# Sheet1.net
KiCad netlist of a schematic drawn in Altium Designer
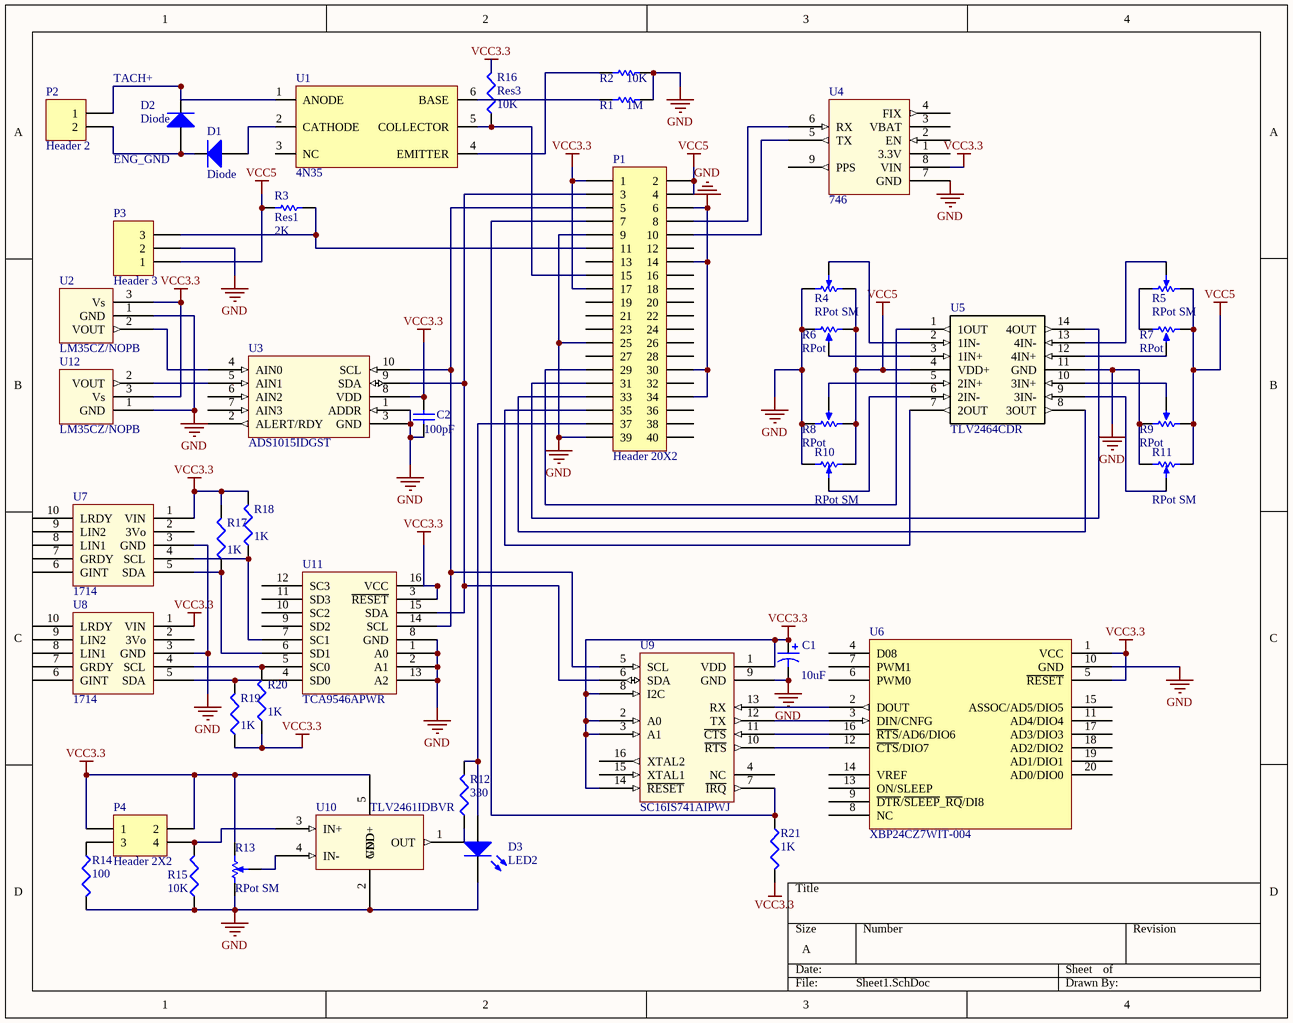
[diagram p0: Sheet1.SchDoc]

(export (version "E")
  (design (tool "Eeschema 10.0.6"))
  (components
    (comp (ref "C1")
      (value "10uF")
      (footprint "C0805")
      (description "Polarized Capacitor (Surface Mount)")
      (fields (field (name "Comment") "Cap Pol3") (field (name "PUBLISHER") "Altium Limited"))
      (libsource (lib "Miscellaneous Devices") (part "Cap Pol3"))
    )
    (comp (ref "C2")
      (value "100pF")
      (footprint "1608[0603]")
      (description "Capacitor (Semiconductor SIM Model)")
      (fields (field (name "Comment") "Cap Semi") (field (name "PUBLISHER") "Altium Limited"))
      (libsource (lib "Miscellaneous Devices") (part "Cap Semi"))
    )
    (comp (ref "D1")
      (value "Diode")
      (footprint "DIODE-0.4")
      (description "Default Diode")
      (fields (field (name "PUBLISHER") "Altium Limited"))
      (libsource (lib "Miscellaneous Devices") (part "Diode"))
    )
    (comp (ref "D2")
      (value "Diode")
      (footprint "DIODE-0.4")
      (description "Default Diode")
      (fields (field (name "PUBLISHER") "Altium Limited"))
      (libsource (lib "Miscellaneous Devices") (part "Diode"))
    )
    (comp (ref "D3")
      (value "LED2")
      (footprint "3.2X1.6X1.1")
      (description "Typical RED, GREEN, YELLOW, AMBER GaAs LED")
      (fields (field (name "PUBLISHER") "Altium Limited"))
      (libsource (lib "Miscellaneous Devices") (part "LED2"))
    )
    (comp (ref "P1")
      (value "Header 20X2")
      (footprint "HDR2X20")
      (description "Header, 20-Pin, Dual row")
      (fields (field (name "PUBLISHER") "Altium Limited"))
      (libsource (lib "Miscellaneous Connectors") (part "Header 20X2"))
    )
    (comp (ref "P2")
      (value "Header 2")
      (footprint "HDR1X2")
      (description "Header, 2-Pin")
      (fields (field (name "PUBLISHER") "Altium Limited"))
      (libsource (lib "Miscellaneous Connectors") (part "Header 2"))
    )
    (comp (ref "P3")
      (value "Header 3")
      (footprint "HDR1X3")
      (description "Header, 3-Pin")
      (fields (field (name "PUBLISHER") "Altium Limited"))
      (libsource (lib "Miscellaneous Connectors") (part "Header 3"))
    )
    (comp (ref "P4")
      (value "Header 2X2")
      (footprint "HDR2X2")
      (description "Header, 2-Pin, Dual row")
      (fields (field (name "PUBLISHER") "Altium Limited"))
      (libsource (lib "Miscellaneous Connectors") (part "Header 2X2"))
    )
    (comp (ref "R1")
      (value "1M")
      (footprint "0402")
      (description "Resistor")
      (fields (field (name "Comment") "Res1") (field (name "PUBLISHER") "Altium Limited"))
      (libsource (lib "Miscellaneous Devices") (part "Res1"))
    )
    (comp (ref "R2")
      (value "10K")
      (footprint "0402")
      (description "Resistor")
      (fields (field (name "Comment") "Res1") (field (name "PUBLISHER") "Altium Limited"))
      (libsource (lib "Miscellaneous Devices") (part "Res1"))
    )
    (comp (ref "R3")
      (value "Res1")
      (footprint "0402")
      (description "Resistor")
      (fields (field (name "ALTIUM_VALUE") "2K") (field (name "PUBLISHER") "Altium Limited"))
      (libsource (lib "Miscellaneous Devices") (part "Res1"))
    )
    (comp (ref "R4")
      (value "RPot SM")
      (footprint "23BR10KLFTR")
      (description "Square Trimming Potentiometer")
      (fields (field (name "PUBLISHER") "Altium Limited"))
      (libsource (lib "Miscellaneous Devices") (part "RPot SM"))
    )
    (comp (ref "R5")
      (value "RPot SM")
      (footprint "23BR10KLFTR")
      (description "Square Trimming Potentiometer")
      (fields (field (name "PUBLISHER") "Altium Limited"))
      (libsource (lib "Miscellaneous Devices") (part "RPot SM"))
    )
    (comp (ref "R6")
      (value "RPot")
      (footprint "VR5")
      (description "Potentiometer")
      (fields (field (name "PUBLISHER") "Altium Limited"))
      (libsource (lib "Miscellaneous Devices") (part "RPot"))
    )
    (comp (ref "R7")
      (value "RPot")
      (footprint "VR5")
      (description "Potentiometer")
      (fields (field (name "PUBLISHER") "Altium Limited"))
      (libsource (lib "Miscellaneous Devices") (part "RPot"))
    )
    (comp (ref "R8")
      (value "RPot")
      (footprint "VR5")
      (description "Potentiometer")
      (fields (field (name "PUBLISHER") "Altium Limited"))
      (libsource (lib "Miscellaneous Devices") (part "RPot"))
    )
    (comp (ref "R9")
      (value "RPot")
      (footprint "VR5")
      (description "Potentiometer")
      (fields (field (name "PUBLISHER") "Altium Limited"))
      (libsource (lib "Miscellaneous Devices") (part "RPot"))
    )
    (comp (ref "R10")
      (value "RPot SM")
      (footprint "23BR10KLFTR")
      (description "Square Trimming Potentiometer")
      (fields (field (name "PUBLISHER") "Altium Limited"))
      (libsource (lib "Miscellaneous Devices") (part "RPot SM"))
    )
    (comp (ref "R11")
      (value "RPot SM")
      (footprint "23BR10KLFTR")
      (description "Square Trimming Potentiometer")
      (fields (field (name "PUBLISHER") "Altium Limited"))
      (libsource (lib "Miscellaneous Devices") (part "RPot SM"))
    )
    (comp (ref "R12")
      (value "330")
      (footprint "0402")
      (description "Resistor")
      (fields (field (name "Comment") "Res3") (field (name "PUBLISHER") "Altium Limited"))
      (libsource (lib "Miscellaneous Devices") (part "Res3"))
    )
    (comp (ref "R13")
      (value "RPot SM")
      (footprint "23BR10KLFTR")
      (description "Square Trimming Potentiometer")
      (fields (field (name "PUBLISHER") "Altium Limited"))
      (libsource (lib "Miscellaneous Devices") (part "RPot SM"))
    )
    (comp (ref "R14")
      (value "100")
      (footprint "0402")
      (description "Resistor")
      (fields (field (name "Comment") "Res3") (field (name "PUBLISHER") "Altium Limited"))
      (libsource (lib "Miscellaneous Devices") (part "Res3"))
    )
    (comp (ref "R15")
      (value "10K")
      (footprint "0402")
      (description "Resistor")
      (fields (field (name "Comment") "Res3") (field (name "PUBLISHER") "Altium Limited"))
      (libsource (lib "Miscellaneous Devices") (part "Res3"))
    )
    (comp (ref "R16")
      (value "Res3")
      (footprint "0402")
      (description "Resistor")
      (fields (field (name "ALTIUM_VALUE") "10K") (field (name "PUBLISHER") "Altium Limited"))
      (libsource (lib "Miscellaneous Devices") (part "Res3"))
    )
    (comp (ref "R17")
      (value "1K")
      (footprint "J1-0603")
      (description "Resistor")
      (fields (field (name "Comment") "Res3") (field (name "PUBLISHER") "Altium Limited"))
      (libsource (lib "Miscellaneous Devices") (part "Res3"))
    )
    (comp (ref "R18")
      (value "1K")
      (footprint "J1-0603")
      (description "Resistor")
      (fields (field (name "Comment") "Res3") (field (name "PUBLISHER") "Altium Limited"))
      (libsource (lib "Miscellaneous Devices") (part "Res3"))
    )
    (comp (ref "R19")
      (value "1K")
      (footprint "J1-0603")
      (description "Resistor")
      (fields (field (name "Comment") "Res3") (field (name "PUBLISHER") "Altium Limited"))
      (libsource (lib "Miscellaneous Devices") (part "Res3"))
    )
    (comp (ref "R20")
      (value "1K")
      (footprint "J1-0603")
      (description "Resistor")
      (fields (field (name "Comment") "Res3") (field (name "PUBLISHER") "Altium Limited"))
      (libsource (lib "Miscellaneous Devices") (part "Res3"))
    )
    (comp (ref "R21")
      (value "1K")
      (footprint "J1-0603")
      (description "Resistor")
      (fields (field (name "Comment") "Res3") (field (name "PUBLISHER") "Altium Limited"))
      (libsource (lib "Miscellaneous Devices") (part "Res3"))
    )
    (comp (ref "U1")
      (value "4N35")
      (footprint "4N35")
      (description "OPTOISO 3.55KV TRANS W/BASE 6DIP")
      (libsource (lib "Baja") (part "4N35"))
    )
    (comp (ref "U2")
      (value "LM35CZ/NOPB")
      (footprint "HDR1X3")
      (description "SENSOR TEMP ANLG VOLT TO-92-3")
      (libsource (lib "") (part "LM35CZ/NOPB_1"))
    )
    (comp (ref "U3")
      (value "ADS1015IDGST")
      (footprint "ADS1015IDGST")
      (description "IC ADC 12BIT I2C W/REF 10-MSOP")
      (libsource (lib "Baja") (part "ADS1015IDGST"))
    )
    (comp (ref "U4")
      (value "746")
      (footprint "HDR1X9")
      (description "GPS BREAKOUT 66CH W/10HZ UPDATES")
      (libsource (lib "Baja") (part "746"))
    )
    (comp (ref "U5")
      (value "TLV2464CDR")
      (footprint "TLV2464CDR")
      (description "IC OPAMP GP 6.4MHZ RRO 14SOIC")
      (libsource (lib "Baja") (part "TLV2464CDR"))
    )
    (comp (ref "U6")
      (value "XBP24CZ7WIT-004")
      (footprint "XBP24CZ7WIT-004")
      (description "RF TXRX MODULE 802.15.4 WIRE ANT")
      (libsource (lib "Baja") (part "XBP24CZ7WIT-004"))
    )
    (comp (ref "U7")
      (value "1714")
      (footprint "HDR1X10")
      (description "9-DOF IMU BREAKOUT BRD")
      (libsource (lib "Baja") (part "1714"))
    )
    (comp (ref "U8")
      (value "1714")
      (footprint "HDR1X10")
      (description "9-DOF IMU BREAKOUT BRD")
      (libsource (lib "Baja") (part "1714"))
    )
    (comp (ref "U9")
      (value "SC16IS741AIPWJ")
      (footprint "SC16IS741AIPWJ")
      (description "IC UART SGL I2C BUS SPI 16TSSOP")
      (libsource (lib "Baja") (part "SC16IS741AIPWJ"))
    )
    (comp (ref "U10")
      (value "TLV2461IDBVR")
      (footprint "TLV2461IDBVR")
      (description "IC OPAMP GP 6.4MHZ RRO SOT23-5")
      (libsource (lib "Baja") (part "TLV2461IDBVR"))
    )
    (comp (ref "U11")
      (value "TCA9546APWR")
      (footprint "TCA9546APWR")
      (description "IC I2C SW 4CH W/RESET 16TSSOP")
      (libsource (lib "Baja") (part "TCA9546APWR"))
    )
    (comp (ref "U12")
      (value "LM35CZ/NOPB")
      (footprint "HDR1X3")
      (description "SENSOR TEMP ANLG VOLT TO-92-3")
      (libsource (lib "Baja") (part "LM35CZ/NOPB"))
    )
  )
  (nets
    (net (code "1") (name "GND") (class "Default")
      (node (ref "C1") (pin "2") (pinfunction "2_2") (pintype "passive"))
      (node (ref "C2") (pin "1") (pinfunction "1_1") (pintype "passive"))
      (node (ref "D3") (pin "2") (pinfunction "K_2") (pintype "passive"))
      (node (ref "P1") (pin "14") (pinfunction "14_14") (pintype "passive"))
      (node (ref "P1") (pin "25") (pinfunction "25_25") (pintype "passive"))
      (node (ref "P1") (pin "30") (pinfunction "30_30") (pintype "passive"))
      (node (ref "P1") (pin "34") (pinfunction "34_34") (pintype "passive"))
      (node (ref "P1") (pin "39") (pinfunction "39_39") (pintype "passive"))
      (node (ref "P1") (pin "6") (pinfunction "6_6") (pintype "passive"))
      (node (ref "P1") (pin "9") (pinfunction "9_9") (pintype "passive"))
      (node (ref "P3") (pin "2") (pinfunction "2_2") (pintype "passive"))
      (node (ref "R1") (pin "1") (pinfunction "1_1") (pintype "passive"))
      (node (ref "R10") (pin "3") (pinfunction "3_3") (pintype "passive"))
      (node (ref "R11") (pin "3") (pinfunction "3_3") (pintype "passive"))
      (node (ref "R13") (pin "3") (pinfunction "3_3") (pintype "passive"))
      (node (ref "R14") (pin "2") (pinfunction "2_2") (pintype "passive"))
      (node (ref "R15") (pin "1") (pinfunction "1_1") (pintype "passive"))
      (node (ref "R2") (pin "1") (pinfunction "1_1") (pintype "passive"))
      (node (ref "R4") (pin "1") (pinfunction "1_1") (pintype "passive"))
      (node (ref "R6") (pin "1") (pinfunction "TOP_1") (pintype "passive"))
      (node (ref "R8") (pin "2") (pinfunction "BOT_2") (pintype "passive"))
      (node (ref "R9") (pin "2") (pinfunction "BOT_2") (pintype "passive"))
      (node (ref "U10") (pin "2") (pinfunction "GND_2") (pintype "power_in"))
      (node (ref "U11") (pin "1") (pinfunction "A0_1") (pintype "passive"))
      (node (ref "U11") (pin "13") (pinfunction "A2_13") (pintype "passive"))
      (node (ref "U11") (pin "2") (pinfunction "A1_2") (pintype "passive"))
      (node (ref "U11") (pin "8") (pinfunction "GND_8") (pintype "power_in"))
      (node (ref "U12") (pin "1") (pinfunction "GND_1") (pintype "power_in"))
      (node (ref "U2") (pin "1") (pinfunction "GND_1") (pintype "power_in"))
      (node (ref "U3") (pin "1") (pinfunction "ADDR_1") (pintype "input"))
      (node (ref "U3") (pin "3") (pinfunction "GND_3") (pintype "power_in"))
      (node (ref "U4") (pin "7") (pinfunction "GND_7") (pintype "power_in"))
      (node (ref "U5") (pin "11") (pinfunction "GND_11") (pintype "power_in"))
      (node (ref "U6") (pin "10") (pinfunction "GND_10") (pintype "power_in"))
      (node (ref "U7") (pin "3") (pinfunction "GND_3") (pintype "power_in"))
      (node (ref "U8") (pin "3") (pinfunction "GND_3") (pintype "power_in"))
      (node (ref "U9") (pin "9") (pinfunction "GND_9") (pintype "power_in"))
    )
    (net (code "2") (name "Net-(D1-A)") (class "Default")
      (node (ref "D1") (pin "1") (pinfunction "A_1") (pintype "passive"))
      (node (ref "U1") (pin "2") (pinfunction "CATHODE_2") (pintype "passive"))
    )
    (net (code "3") (name "Net-(D1-K)") (class "Default")
      (node (ref "D1") (pin "2") (pinfunction "K_2") (pintype "passive"))
      (node (ref "D2") (pin "1") (pinfunction "A_1") (pintype "passive"))
      (node (ref "P2") (pin "2") (pinfunction "2_2") (pintype "passive"))
    )
    (net (code "4") (name "Net-(D2-K)") (class "Default")
      (node (ref "D2") (pin "2") (pinfunction "K_2") (pintype "passive"))
      (node (ref "P2") (pin "1") (pinfunction "1_1") (pintype "passive"))
      (node (ref "U1") (pin "1") (pinfunction "ANODE_1") (pintype "passive"))
    )
    (net (code "5") (name "Net-(D3-A)") (class "Default")
      (node (ref "D3") (pin "1") (pinfunction "A_1") (pintype "passive"))
      (node (ref "P1") (pin "37") (pinfunction "37_37") (pintype "passive"))
      (node (ref "R12") (pin "2") (pinfunction "2_2") (pintype "passive"))
    )
    (net (code "6") (name "Net-(P1-Pad11)") (class "Default")
      (node (ref "P1") (pin "11") (pinfunction "11_11") (pintype "passive"))
      (node (ref "P3") (pin "3") (pinfunction "3_3") (pintype "passive"))
      (node (ref "R3") (pin "2") (pinfunction "2_2") (pintype "passive"))
    )
    (net (code "7") (name "Net-(P4-Pad3)") (class "Default")
      (node (ref "P4") (pin "3") (pinfunction "3_3") (pintype "passive"))
      (node (ref "R14") (pin "1") (pinfunction "1_1") (pintype "passive"))
    )
    (net (code "8") (name "Net-(R6-TAP)") (class "Default")
      (node (ref "R6") (pin "3") (pinfunction "TAP_3") (pintype "passive"))
      (node (ref "U5") (pin "3") (pinfunction "1IN+_3") (pintype "input"))
    )
    (net (code "9") (name "Net-(R7-TAP)") (class "Default")
      (node (ref "R7") (pin "3") (pinfunction "TAP_3") (pintype "passive"))
      (node (ref "U5") (pin "12") (pinfunction "4IN+_12") (pintype "input"))
    )
    (net (code "10") (name "Net-(R7-TOP)") (class "Default")
      (node (ref "R5") (pin "1") (pinfunction "1_1") (pintype "passive"))
      (node (ref "R7") (pin "1") (pinfunction "TOP_1") (pintype "passive"))
    )
    (net (code "11") (name "Net-(R8-TAP)") (class "Default")
      (node (ref "R8") (pin "3") (pinfunction "TAP_3") (pintype "passive"))
      (node (ref "U5") (pin "5") (pinfunction "2IN+_5") (pintype "input"))
    )
    (net (code "12") (name "Net-(R9-TAP)") (class "Default")
      (node (ref "R9") (pin "3") (pinfunction "TAP_3") (pintype "passive"))
      (node (ref "U5") (pin "10") (pinfunction "3IN+_10") (pintype "input"))
    )
    (net (code "13") (name "Net-(U1-BASE)") (class "Default")
      (node (ref "R1") (pin "2") (pinfunction "2_2") (pintype "passive"))
      (node (ref "U1") (pin "6") (pinfunction "BASE_6") (pintype "passive"))
    )
    (net (code "14") (name "Net-(U1-COLLECTOR)") (class "Default")
      (node (ref "P1") (pin "15") (pinfunction "15_15") (pintype "passive"))
      (node (ref "R16") (pin "1") (pinfunction "1_1") (pintype "passive"))
      (node (ref "U1") (pin "5") (pinfunction "COLLECTOR_5") (pintype "passive"))
    )
    (net (code "15") (name "Net-(U1-EMITTER)") (class "Default")
      (node (ref "R2") (pin "2") (pinfunction "2_2") (pintype "passive"))
      (node (ref "U1") (pin "4") (pinfunction "EMITTER_4") (pintype "passive"))
    )
    (net (code "16") (name "Net-(U2-VOUT)") (class "Default")
      (node (ref "U2") (pin "2") (pinfunction "VOUT_2") (pintype "output"))
      (node (ref "U3") (pin "4") (pinfunction "AIN0_4") (pintype "input"))
    )
    (net (code "17") (name "Net-(U4-RX)") (class "Default")
      (node (ref "P1") (pin "8") (pinfunction "8_8") (pintype "passive"))
      (node (ref "U4") (pin "6") (pinfunction "RX_6") (pintype "input"))
    )
    (net (code "18") (name "Net-(U4-TX)") (class "Default")
      (node (ref "P1") (pin "10") (pinfunction "10_10") (pintype "passive"))
      (node (ref "U4") (pin "5") (pinfunction "TX_5") (pintype "output"))
    )
    (net (code "19") (name "Net-(U5-1IN-)") (class "Default")
      (node (ref "R4") (pin "2") (pinfunction "2_2") (pintype "passive"))
      (node (ref "U5") (pin "2") (pinfunction "1IN-_2") (pintype "input"))
    )
    (net (code "20") (name "Net-(U5-1OUT)") (class "Default")
      (node (ref "P1") (pin "29") (pinfunction "29_29") (pintype "passive"))
      (node (ref "U5") (pin "1") (pinfunction "1OUT_1") (pintype "output"))
    )
    (net (code "21") (name "Net-(U5-2IN-)") (class "Default")
      (node (ref "R10") (pin "2") (pinfunction "2_2") (pintype "passive"))
      (node (ref "U5") (pin "6") (pinfunction "2IN-_6") (pintype "input"))
    )
    (net (code "22") (name "Net-(U5-2OUT)") (class "Default")
      (node (ref "P1") (pin "35") (pinfunction "35_35") (pintype "passive"))
      (node (ref "U5") (pin "7") (pinfunction "2OUT_7") (pintype "output"))
    )
    (net (code "23") (name "Net-(U5-3IN-)") (class "Default")
      (node (ref "R11") (pin "2") (pinfunction "2_2") (pintype "passive"))
      (node (ref "U5") (pin "9") (pinfunction "3IN-_9") (pintype "input"))
    )
    (net (code "24") (name "Net-(U5-3OUT)") (class "Default")
      (node (ref "P1") (pin "33") (pinfunction "33_33") (pintype "passive"))
      (node (ref "U5") (pin "8") (pinfunction "3OUT_8") (pintype "output"))
    )
    (net (code "25") (name "Net-(U5-4IN-)") (class "Default")
      (node (ref "R5") (pin "2") (pinfunction "2_2") (pintype "passive"))
      (node (ref "U5") (pin "13") (pinfunction "4IN-_13") (pintype "input"))
    )
    (net (code "26") (name "Net-(U5-4OUT)") (class "Default")
      (node (ref "P1") (pin "31") (pinfunction "31_31") (pintype "passive"))
      (node (ref "U5") (pin "14") (pinfunction "4OUT_14") (pintype "output"))
    )
    (net (code "27") (name "Net-(U6-DIN{slash}CNFG)") (class "Default")
      (node (ref "U6") (pin "3") (pinfunction "DIN/CNFG_3") (pintype "input"))
      (node (ref "U9") (pin "12") (pinfunction "TX_12") (pintype "output"))
    )
    (net (code "28") (name "Net-(U6-DOUT)") (class "Default")
      (node (ref "U6") (pin "2") (pinfunction "DOUT_2") (pintype "output"))
      (node (ref "U9") (pin "13") (pinfunction "RX_13") (pintype "input"))
    )
    (net (code "29") (name "Net-(U6-~{CTS}{slash}DIO7)") (class "Default")
      (node (ref "U6") (pin "12") (pinfunction "~{CTS}/DIO7_12") (pintype "passive"))
      (node (ref "U9") (pin "10") (pinfunction "~{RTS}_10") (pintype "output"))
    )
    (net (code "30") (name "Net-(U6-~{RTS}{slash}AD6{slash}DIO6)") (class "Default")
      (node (ref "U6") (pin "16") (pinfunction "~{RTS}/AD6/DIO6_16") (pintype "passive"))
      (node (ref "U9") (pin "11") (pinfunction "~{CTS}_11") (pintype "input"))
    )
    (net (code "31") (name "Net-(U9-~{IRQ})") (class "Default")
      (node (ref "P1") (pin "7") (pinfunction "7_7") (pintype "passive"))
      (node (ref "R21") (pin "1") (pinfunction "1_1") (pintype "passive"))
      (node (ref "U9") (pin "7") (pinfunction "~{IRQ}_7") (pintype "output"))
    )
    (net (code "32") (name "Net-(U10-IN+)") (class "Default")
      (node (ref "P4") (pin "4") (pinfunction "4_4") (pintype "passive"))
      (node (ref "R15") (pin "2") (pinfunction "2_2") (pintype "passive"))
      (node (ref "U10") (pin "3") (pinfunction "IN+_3") (pintype "input"))
    )
    (net (code "33") (name "Net-(U10-IN-)") (class "Default")
      (node (ref "R13") (pin "2") (pinfunction "2_2") (pintype "passive"))
      (node (ref "U10") (pin "4") (pinfunction "IN-_4") (pintype "input"))
    )
    (net (code "34") (name "Net-(U10-OUT)") (class "Default")
      (node (ref "R12") (pin "1") (pinfunction "1_1") (pintype "passive"))
      (node (ref "U10") (pin "1") (pinfunction "OUT_1") (pintype "output"))
    )
    (net (code "35") (name "Net-(U11-SC0)") (class "Default")
      (node (ref "R20") (pin "2") (pinfunction "2_2") (pintype "passive"))
      (node (ref "U11") (pin "5") (pinfunction "SC0_5") (pintype "passive"))
      (node (ref "U8") (pin "4") (pinfunction "SCL_4") (pintype "passive"))
    )
    (net (code "36") (name "Net-(U11-SC1)") (class "Default")
      (node (ref "R18") (pin "1") (pinfunction "1_1") (pintype "passive"))
      (node (ref "U11") (pin "7") (pinfunction "SC1_7") (pintype "passive"))
      (node (ref "U7") (pin "4") (pinfunction "SCL_4") (pintype "passive"))
    )
    (net (code "37") (name "Net-(U11-SCL)") (class "Default")
      (node (ref "P1") (pin "5") (pinfunction "5_5") (pintype "passive"))
      (node (ref "U11") (pin "14") (pinfunction "SCL_14") (pintype "passive"))
      (node (ref "U3") (pin "10") (pinfunction "SCL_10") (pintype "input"))
      (node (ref "U9") (pin "5") (pinfunction "SCL_5") (pintype "input"))
    )
    (net (code "38") (name "Net-(U11-SD0)") (class "Default")
      (node (ref "R19") (pin "2") (pinfunction "2_2") (pintype "passive"))
      (node (ref "U11") (pin "4") (pinfunction "SD0_4") (pintype "passive"))
      (node (ref "U8") (pin "5") (pinfunction "SDA_5") (pintype "passive"))
    )
    (net (code "39") (name "Net-(U11-SD1)") (class "Default")
      (node (ref "R17") (pin "1") (pinfunction "1_1") (pintype "passive"))
      (node (ref "U11") (pin "6") (pinfunction "SD1_6") (pintype "passive"))
      (node (ref "U7") (pin "5") (pinfunction "SDA_5") (pintype "passive"))
    )
    (net (code "40") (name "Net-(U11-SDA)") (class "Default")
      (node (ref "P1") (pin "3") (pinfunction "3_3") (pintype "passive"))
      (node (ref "U11") (pin "15") (pinfunction "SDA_15") (pintype "passive"))
      (node (ref "U3") (pin "9") (pinfunction "SDA_9") (pintype "bidirectional"))
      (node (ref "U9") (pin "6") (pinfunction "SDA_6") (pintype "bidirectional"))
    )
    (net (code "41") (name "Net-(U12-VOUT)") (class "Default")
      (node (ref "U12") (pin "2") (pinfunction "VOUT_2") (pintype "output"))
      (node (ref "U3") (pin "5") (pinfunction "AIN1_5") (pintype "input"))
    )
    (net (code "42") (name "VCC3.3") (class "Default")
      (node (ref "C1") (pin "1") (pinfunction "1_1") (pintype "passive"))
      (node (ref "C2") (pin "2") (pinfunction "2_2") (pintype "passive"))
      (node (ref "P1") (pin "1") (pinfunction "1_1") (pintype "passive"))
      (node (ref "P1") (pin "17") (pinfunction "17_17") (pintype "passive"))
      (node (ref "P4") (pin "1") (pinfunction "1_1") (pintype "passive"))
      (node (ref "P4") (pin "2") (pinfunction "2_2") (pintype "passive"))
      (node (ref "R13") (pin "1") (pinfunction "1_1") (pintype "passive"))
      (node (ref "R16") (pin "2") (pinfunction "2_2") (pintype "passive"))
      (node (ref "R17") (pin "2") (pinfunction "2_2") (pintype "passive"))
      (node (ref "R18") (pin "2") (pinfunction "2_2") (pintype "passive"))
      (node (ref "R19") (pin "1") (pinfunction "1_1") (pintype "passive"))
      (node (ref "R20") (pin "1") (pinfunction "1_1") (pintype "passive"))
      (node (ref "R21") (pin "2") (pinfunction "2_2") (pintype "passive"))
      (node (ref "U10") (pin "5") (pinfunction "VDD+_5") (pintype "power_in"))
      (node (ref "U11") (pin "16") (pinfunction "VCC_16") (pintype "power_in"))
      (node (ref "U11") (pin "3") (pinfunction "~{RESET}_3") (pintype "passive"))
      (node (ref "U12") (pin "3") (pinfunction "Vs_3") (pintype "power_in"))
      (node (ref "U2") (pin "3") (pinfunction "Vs_3") (pintype "power_in"))
      (node (ref "U3") (pin "8") (pinfunction "VDD_8") (pintype "power_in"))
      (node (ref "U4") (pin "8") (pinfunction "VIN_8") (pintype "power_in"))
      (node (ref "U6") (pin "1") (pinfunction "VCC_1") (pintype "power_in"))
      (node (ref "U6") (pin "5") (pinfunction "~{RESET}_5") (pintype "passive"))
      (node (ref "U7") (pin "1") (pinfunction "VIN_1") (pintype "power_in"))
      (node (ref "U8") (pin "1") (pinfunction "VIN_1") (pintype "power_in"))
      (node (ref "U9") (pin "1") (pinfunction "VDD_1") (pintype "power_in"))
      (node (ref "U9") (pin "14") (pinfunction "~{RESET}_14") (pintype "input"))
      (node (ref "U9") (pin "2") (pinfunction "A0_2") (pintype "input"))
      (node (ref "U9") (pin "3") (pinfunction "A1_3") (pintype "input"))
      (node (ref "U9") (pin "8") (pinfunction "I2C_8") (pintype "input"))
    )
    (net (code "43") (name "VCC5") (class "Default")
      (node (ref "P1") (pin "2") (pinfunction "2_2") (pintype "passive"))
      (node (ref "P1") (pin "4") (pinfunction "4_4") (pintype "passive"))
      (node (ref "P3") (pin "1") (pinfunction "1_1") (pintype "passive"))
      (node (ref "R10") (pin "1") (pinfunction "1_1") (pintype "passive"))
      (node (ref "R11") (pin "1") (pinfunction "1_1") (pintype "passive"))
      (node (ref "R3") (pin "1") (pinfunction "1_1") (pintype "passive"))
      (node (ref "R4") (pin "3") (pinfunction "3_3") (pintype "passive"))
      (node (ref "R5") (pin "3") (pinfunction "3_3") (pintype "passive"))
      (node (ref "R6") (pin "2") (pinfunction "BOT_2") (pintype "passive"))
      (node (ref "R7") (pin "2") (pinfunction "BOT_2") (pintype "passive"))
      (node (ref "R8") (pin "1") (pinfunction "TOP_1") (pintype "passive"))
      (node (ref "R9") (pin "1") (pinfunction "TOP_1") (pintype "passive"))
      (node (ref "U5") (pin "4") (pinfunction "VDD+_4") (pintype "power_in"))
    )
    (net (code "44") (name "unconnected-(P1-Pad12)") (class "Default")
      (node (ref "P1") (pin "12") (pinfunction "12_12") (pintype "passive"))
    )
    (net (code "45") (name "unconnected-(P1-Pad13)") (class "Default")
      (node (ref "P1") (pin "13") (pinfunction "13_13") (pintype "passive"))
    )
    (net (code "46") (name "unconnected-(P1-Pad16)") (class "Default")
      (node (ref "P1") (pin "16") (pinfunction "16_16") (pintype "passive"))
    )
    (net (code "47") (name "unconnected-(P1-Pad18)") (class "Default")
      (node (ref "P1") (pin "18") (pinfunction "18_18") (pintype "passive"))
    )
    (net (code "48") (name "unconnected-(P1-Pad19)") (class "Default")
      (node (ref "P1") (pin "19") (pinfunction "19_19") (pintype "passive"))
    )
    (net (code "49") (name "unconnected-(P1-Pad20)") (class "Default")
      (node (ref "P1") (pin "20") (pinfunction "20_20") (pintype "passive"))
    )
    (net (code "50") (name "unconnected-(P1-Pad21)") (class "Default")
      (node (ref "P1") (pin "21") (pinfunction "21_21") (pintype "passive"))
    )
    (net (code "51") (name "unconnected-(P1-Pad22)") (class "Default")
      (node (ref "P1") (pin "22") (pinfunction "22_22") (pintype "passive"))
    )
    (net (code "52") (name "unconnected-(P1-Pad23)") (class "Default")
      (node (ref "P1") (pin "23") (pinfunction "23_23") (pintype "passive"))
    )
    (net (code "53") (name "unconnected-(P1-Pad24)") (class "Default")
      (node (ref "P1") (pin "24") (pinfunction "24_24") (pintype "passive"))
    )
    (net (code "54") (name "unconnected-(P1-Pad26)") (class "Default")
      (node (ref "P1") (pin "26") (pinfunction "26_26") (pintype "passive"))
    )
    (net (code "55") (name "unconnected-(P1-Pad27)") (class "Default")
      (node (ref "P1") (pin "27") (pinfunction "27_27") (pintype "passive"))
    )
    (net (code "56") (name "unconnected-(P1-Pad28)") (class "Default")
      (node (ref "P1") (pin "28") (pinfunction "28_28") (pintype "passive"))
    )
    (net (code "57") (name "unconnected-(P1-Pad32)") (class "Default")
      (node (ref "P1") (pin "32") (pinfunction "32_32") (pintype "passive"))
    )
    (net (code "58") (name "unconnected-(P1-Pad36)") (class "Default")
      (node (ref "P1") (pin "36") (pinfunction "36_36") (pintype "passive"))
    )
    (net (code "59") (name "unconnected-(P1-Pad38)") (class "Default")
      (node (ref "P1") (pin "38") (pinfunction "38_38") (pintype "passive"))
    )
    (net (code "60") (name "unconnected-(P1-Pad40)") (class "Default")
      (node (ref "P1") (pin "40") (pinfunction "40_40") (pintype "passive"))
    )
    (net (code "61") (name "unconnected-(U1-NC-Pad3)") (class "Default")
      (node (ref "U1") (pin "3") (pinfunction "NC_3") (pintype "passive"))
    )
    (net (code "62") (name "unconnected-(U3-AIN2-Pad6)") (class "Default")
      (node (ref "U3") (pin "6") (pinfunction "AIN2_6") (pintype "input"))
    )
    (net (code "63") (name "unconnected-(U3-AIN3-Pad7)") (class "Default")
      (node (ref "U3") (pin "7") (pinfunction "AIN3_7") (pintype "input"))
    )
    (net (code "64") (name "unconnected-(U3-ALERT{slash}RDY-Pad2)") (class "Default")
      (node (ref "U3") (pin "2") (pinfunction "ALERT/RDY_2") (pintype "output"))
    )
    (net (code "65") (name "unconnected-(U4-3.3V-Pad1)") (class "Default")
      (node (ref "U4") (pin "1") (pinfunction "3.3V_1") (pintype "power_in"))
    )
    (net (code "66") (name "unconnected-(U4-EN-Pad2)") (class "Default")
      (node (ref "U4") (pin "2") (pinfunction "EN_2") (pintype "input"))
    )
    (net (code "67") (name "unconnected-(U4-FIX-Pad4)") (class "Default")
      (node (ref "U4") (pin "4") (pinfunction "FIX_4") (pintype "output"))
    )
    (net (code "68") (name "unconnected-(U4-PPS-Pad9)") (class "Default")
      (node (ref "U4") (pin "9") (pinfunction "PPS_9") (pintype "output"))
    )
    (net (code "69") (name "unconnected-(U4-VBAT-Pad3)") (class "Default")
      (node (ref "U4") (pin "3") (pinfunction "VBAT_3") (pintype "passive"))
    )
    (net (code "70") (name "unconnected-(U6-AD0{slash}DIO0-Pad20)") (class "Default")
      (node (ref "U6") (pin "20") (pinfunction "AD0/DIO0_20") (pintype "passive"))
    )
    (net (code "71") (name "unconnected-(U6-AD1{slash}DIO1-Pad19)") (class "Default")
      (node (ref "U6") (pin "19") (pinfunction "AD1/DIO1_19") (pintype "passive"))
    )
    (net (code "72") (name "unconnected-(U6-AD2{slash}DIO2-Pad18)") (class "Default")
      (node (ref "U6") (pin "18") (pinfunction "AD2/DIO2_18") (pintype "passive"))
    )
    (net (code "73") (name "unconnected-(U6-AD3{slash}DIO3-Pad17)") (class "Default")
      (node (ref "U6") (pin "17") (pinfunction "AD3/DIO3_17") (pintype "passive"))
    )
    (net (code "74") (name "unconnected-(U6-AD4{slash}DIO4-Pad11)") (class "Default")
      (node (ref "U6") (pin "11") (pinfunction "AD4/DIO4_11") (pintype "passive"))
    )
    (net (code "75") (name "unconnected-(U6-ASSOC{slash}AD5{slash}DIO5-Pad15)") (class "Default")
      (node (ref "U6") (pin "15") (pinfunction "ASSOC/AD5/DIO5_15") (pintype "passive"))
    )
    (net (code "76") (name "unconnected-(U6-D08-Pad4)") (class "Default")
      (node (ref "U6") (pin "4") (pinfunction "D08_4") (pintype "passive"))
    )
    (net (code "77") (name "unconnected-(U6-NC-Pad8)") (class "Default")
      (node (ref "U6") (pin "8") (pinfunction "NC_8") (pintype "passive"))
    )
    (net (code "78") (name "unconnected-(U6-ON{slash}SLEEP-Pad13)") (class "Default")
      (node (ref "U6") (pin "13") (pinfunction "ON/SLEEP_13") (pintype "passive"))
    )
    (net (code "79") (name "unconnected-(U6-PWM0-Pad6)") (class "Default")
      (node (ref "U6") (pin "6") (pinfunction "PWM0_6") (pintype "passive"))
    )
    (net (code "80") (name "unconnected-(U6-PWM1-Pad7)") (class "Default")
      (node (ref "U6") (pin "7") (pinfunction "PWM1_7") (pintype "passive"))
    )
    (net (code "81") (name "unconnected-(U6-VREF-Pad14)") (class "Default")
      (node (ref "U6") (pin "14") (pinfunction "VREF_14") (pintype "passive"))
    )
    (net (code "82") (name "unconnected-(U6-~{DTR}{slash}~{SLEEP}_~{RQ}{slash}DI8-Pad9)") (class "Default")
      (node (ref "U6") (pin "9") (pinfunction "~{DTR}/~{SLEEP}_~{RQ}/DI8_9") (pintype "passive"))
    )
    (net (code "83") (name "unconnected-(U7-3Vo-Pad2)") (class "Default")
      (node (ref "U7") (pin "2") (pinfunction "3Vo_2") (pintype "power_in"))
    )
    (net (code "84") (name "unconnected-(U7-GINT-Pad6)") (class "Default")
      (node (ref "U7") (pin "6") (pinfunction "GINT_6") (pintype "passive"))
    )
    (net (code "85") (name "unconnected-(U7-GRDY-Pad7)") (class "Default")
      (node (ref "U7") (pin "7") (pinfunction "GRDY_7") (pintype "passive"))
    )
    (net (code "86") (name "unconnected-(U7-LIN1-Pad8)") (class "Default")
      (node (ref "U7") (pin "8") (pinfunction "LIN1_8") (pintype "passive"))
    )
    (net (code "87") (name "unconnected-(U7-LIN2-Pad9)") (class "Default")
      (node (ref "U7") (pin "9") (pinfunction "LIN2_9") (pintype "passive"))
    )
    (net (code "88") (name "unconnected-(U7-LRDY-Pad10)") (class "Default")
      (node (ref "U7") (pin "10") (pinfunction "LRDY_10") (pintype "passive"))
    )
    (net (code "89") (name "unconnected-(U8-3Vo-Pad2)") (class "Default")
      (node (ref "U8") (pin "2") (pinfunction "3Vo_2") (pintype "power_in"))
    )
    (net (code "90") (name "unconnected-(U8-GINT-Pad6)") (class "Default")
      (node (ref "U8") (pin "6") (pinfunction "GINT_6") (pintype "passive"))
    )
    (net (code "91") (name "unconnected-(U8-GRDY-Pad7)") (class "Default")
      (node (ref "U8") (pin "7") (pinfunction "GRDY_7") (pintype "passive"))
    )
    (net (code "92") (name "unconnected-(U8-LIN1-Pad8)") (class "Default")
      (node (ref "U8") (pin "8") (pinfunction "LIN1_8") (pintype "passive"))
    )
    (net (code "93") (name "unconnected-(U8-LIN2-Pad9)") (class "Default")
      (node (ref "U8") (pin "9") (pinfunction "LIN2_9") (pintype "passive"))
    )
    (net (code "94") (name "unconnected-(U8-LRDY-Pad10)") (class "Default")
      (node (ref "U8") (pin "10") (pinfunction "LRDY_10") (pintype "passive"))
    )
    (net (code "95") (name "unconnected-(U9-NC-Pad4)") (class "Default")
      (node (ref "U9") (pin "4") (pinfunction "NC_4") (pintype "passive"))
    )
    (net (code "96") (name "unconnected-(U9-XTAL1-Pad15)") (class "Default")
      (node (ref "U9") (pin "15") (pinfunction "XTAL1_15") (pintype "input"))
    )
    (net (code "97") (name "unconnected-(U9-XTAL2-Pad16)") (class "Default")
      (node (ref "U9") (pin "16") (pinfunction "XTAL2_16") (pintype "output"))
    )
    (net (code "98") (name "unconnected-(U11-SC2-Pad10)") (class "Default")
      (node (ref "U11") (pin "10") (pinfunction "SC2_10") (pintype "passive"))
    )
    (net (code "99") (name "unconnected-(U11-SC3-Pad12)") (class "Default")
      (node (ref "U11") (pin "12") (pinfunction "SC3_12") (pintype "passive"))
    )
    (net (code "100") (name "unconnected-(U11-SD2-Pad9)") (class "Default")
      (node (ref "U11") (pin "9") (pinfunction "SD2_9") (pintype "passive"))
    )
    (net (code "101") (name "unconnected-(U11-SD3-Pad11)") (class "Default")
      (node (ref "U11") (pin "11") (pinfunction "SD3_11") (pintype "passive"))
    )
  )
)
